# Power_Decoupling.net
KiCad netlist of a schematic drawn in Altium Designer
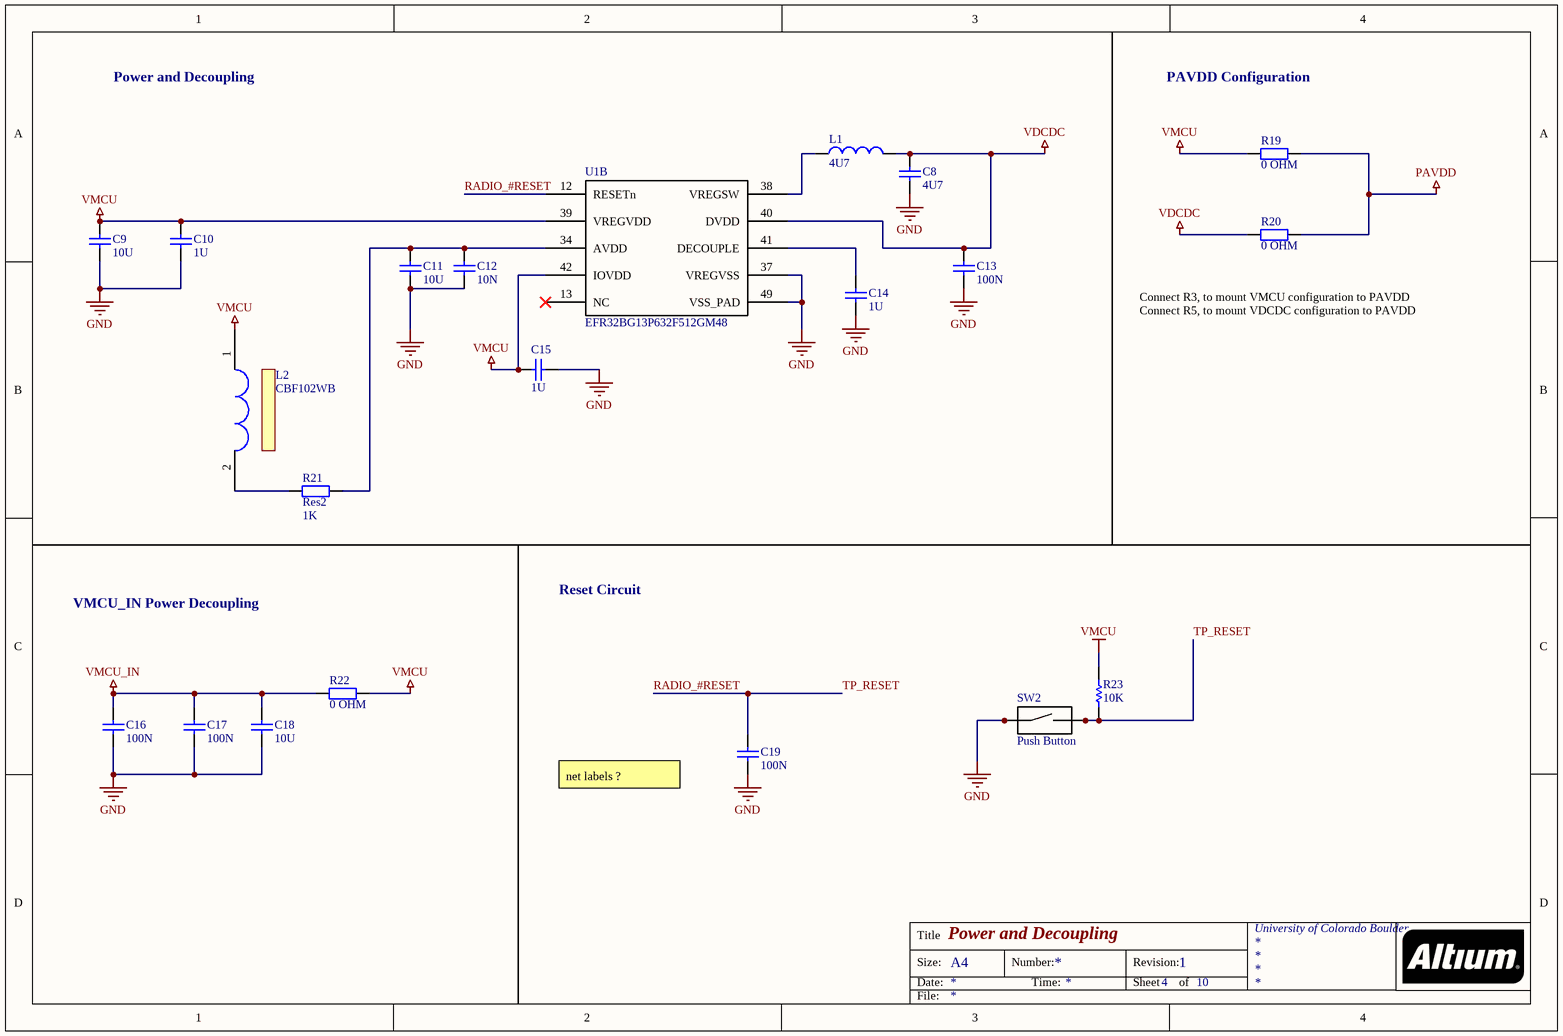
[diagram p0: Power_Decoupling.SchDoc]

(export (version "E")
  (design (tool "Eeschema 10.0.6"))
  (components
    (comp (ref "C8")
      (value "4U7")
      (footprint "1608[0603]")
      (description "CAP CER 4.7UF 25V X5R 0603")
      (fields
        (field (name "DIGI-KEY PART NUMBER") "1276-1900-1-ND")
        (field (name "MANUFACTURER") "Samsung Electro-Mechanics")
      )
      (libsource (lib "Miscellaneous Devices") (part "Cap"))
    )
    (comp (ref "C9")
      (value "10U")
      (footprint "1608[0603]")
      (description "CAP CER 10UF 6.3V X5R 0603")
      (fields
        (field (name "DIGI-KEY PART NUMBER") "1276-1119-1-ND")
        (field (name "MANUFACTURER") "Samsung Electro-Mechanics")
      )
      (libsource (lib "Miscellaneous Devices") (part "Cap"))
    )
    (comp (ref "C10")
      (value "1U")
      (footprint "RAD-0.3")
      (description "CAP CER 1UF 25V X5R 0603")
      (fields
        (field (name "DIGI-KEY PART NUMBER") "1276-1102-1-ND")
        (field (name "MANUFACTURER") "Samsung Electro-Mechanics")
      )
      (libsource (lib "Miscellaneous Devices") (part "Cap"))
    )
    (comp (ref "C11")
      (value "10U")
      (footprint "1608[0603]")
      (description "CAP CER 10UF 6.3V X5R 0603")
      (fields
        (field (name "DIGI-KEY PART NUMBER") "1276-1119-1-ND")
        (field (name "MANUFACTURER") "Samsung Electro-Mechanics")
      )
      (libsource (lib "Miscellaneous Devices") (part "Cap"))
    )
    (comp (ref "C12")
      (value "10N")
      (footprint "1608[0603]")
      (description "CAP CER 10000PF 16V X7R 0603")
      (fields (field (name "DIGI-KEY PART NUMBER") "399-7841-1-ND") (field (name "MANUFACTURER") "KEMET"))
      (libsource (lib "Miscellaneous Devices") (part "Cap"))
    )
    (comp (ref "C13")
      (value "100N")
      (footprint "1608[0603]")
      (description "CAP CER 0.1UF 16V X7R 0603")
      (fields
        (field (name "DIGI-KEY PART NUMBER") "1276-1005-1-ND")
        (field (name "MANUFACTURER") "Samsung Electro-Mechanics")
      )
      (libsource (lib "Miscellaneous Devices") (part "Cap"))
    )
    (comp (ref "C14")
      (value "1U")
      (footprint "1608[0603]")
      (description "CAP CER 1UF 25V X5R 0603")
      (fields
        (field (name "DIGI-KEY PART NUMBER") "1276-1102-1-ND")
        (field (name "MANUFACTURER") "Samsung Electro-Mechanics")
      )
      (libsource (lib "Miscellaneous Devices") (part "Cap"))
    )
    (comp (ref "C15")
      (value "1U")
      (footprint "1608[0603]")
      (description "CAP CER 1UF 25V X5R 0603")
      (fields
        (field (name "DIGI-KEY PART NUMBER") "1276-1102-1-ND")
        (field (name "MANUFACTURER") "Samsung Electro-Mechanics")
      )
      (libsource (lib "Miscellaneous Devices") (part "Cap"))
    )
    (comp (ref "C16")
      (value "100N")
      (footprint "1608[0603]")
      (description "CAP CER 0.1UF 16V X7R 0603")
      (fields
        (field (name "DIGI-KEY PART NUMBER") "1276-1005-1-ND")
        (field (name "MANUFACTURER") "Samsung Electro-Mechanics")
      )
      (libsource (lib "Miscellaneous Devices") (part "Cap"))
    )
    (comp (ref "C17")
      (value "100N")
      (footprint "1608[0603]")
      (description "CAP CER 0.1UF 16V X7R 0603")
      (fields
        (field (name "DIGI-KEY PART NUMBER") "1276-1005-1-ND")
        (field (name "MANUFACTURER") "Samsung Electro-Mechanics")
      )
      (libsource (lib "Miscellaneous Devices") (part "Cap"))
    )
    (comp (ref "C18")
      (value "10U")
      (footprint "1608[0603]")
      (description "CAP CER 10UF 6.3V X5R 0603")
      (fields
        (field (name "DIGI-KEY PART NUMBER") "490-12538-1-ND")
        (field (name "MANUFACTURER") "Murata Electronics")
      )
      (libsource (lib "Miscellaneous Devices") (part "Cap"))
    )
    (comp (ref "C19")
      (value "100N")
      (footprint "1608[0603]")
      (description "CAP CER 0.1UF 16V X7R 0603")
      (fields
        (field (name "DIGI-KEY PART NUMBER") "1276-1005-1-ND")
        (field (name "MANUFACTURER") "Samsung Electro-Mechanics")
      )
      (libsource (lib "Miscellaneous Devices") (part "Cap"))
    )
    (comp (ref "L1")
      (value "4U7")
      (footprint "0402-A")
      (description "FIXED IND 4.7UH 1.25A 130 MOHM")
      (fields
        (field (name "MOUSER PART NUMBER") "81-LQH3NPN4R7MM0L")
        (field (name "MANUFACTURER") "Murata Electronics")
      )
      (libsource (lib "Miscellaneous Devices") (part "Inductor"))
    )
    (comp (ref "L2")
      (value "CBF102WB")
      (footprint "*CAPC0603X56N")
      (description "FERRITE BEAD 1 KOHM 0603 1LN")
      (fields
        (field (name "DIGI-KEY PART NUMBER") "732-4484-1-ND")
        (field (name "MANUFACTURER") "Wurth Electronics Inc.")
      )
      (libsource (lib "LPEDT_Project_Library") (part "COMPONENT_1"))
    )
    (comp (ref "R19")
      (value "0 OHM")
      (footprint "AXIAL-0.4")
      (description "RES SMD 0 OHM JUMPER 1/10W 0603")
      (fields (field (name "DIGI-KEY PART NUMBER") "311-0.0GRCT-ND") (field (name "MANUFACTURER") "Yageo"))
      (libsource (lib "Miscellaneous Devices") (part "Res2"))
    )
    (comp (ref "R20")
      (value "0 OHM")
      (footprint "AXIAL-0.4")
      (description "RES SMD 0 OHM JUMPER 1/10W 0603")
      (fields (field (name "DIGI-KEY PART NUMBER") "311-0.0GRCT-ND") (field (name "MANUFACTURER") "Yageo"))
      (libsource (lib "Miscellaneous Devices") (part "Res2"))
    )
    (comp (ref "R21")
      (value "Res2")
      (footprint "AXIAL-0.4")
      (description "Resistor")
      (fields (field (name "ALTIUM_VALUE") "1K") (field (name "PUBLISHER") "Altium Limited"))
      (libsource (lib "Miscellaneous Devices") (part "Res2"))
    )
    (comp (ref "R22")
      (value "0 OHM")
      (footprint "1608[0603]")
      (description "RES SMD 0 OHM JUMPER 1/10W 0603")
      (fields (field (name "DIGI-KEY PART NUMBER") "311-0.0GRCT-ND") (field (name "MANUFACTURER") "Yageo"))
      (libsource (lib "Miscellaneous Devices") (part "Res2"))
    )
    (comp (ref "R23")
      (value "10K")
      (footprint "1608[0603]")
      (description "RES 10K OHM 1% 1/8W 0603")
      (fields
        (field (name "DIGI-KEY PART NUMBER") "RNCP0603FTD10K0CT-ND")
        (field (name "MANUFACTURER") "Stackpole Electronics Inc")
      )
      (libsource (lib "Miscellaneous Devices") (part "Res1"))
    )
    (comp (ref "SW2")
      (value "Push Button")
      (footprint "Push Button")
      (description "SWITCH TACTILE SPST-NO 0.05A 24V")
      (fields
        (field (name "DIGI-KEY PART NUMBER") "450-2058-1-ND")
        (field (name "MANUFACTURER") "TE Connectivity ALCOSWITCH Switches")
      )
      (libsource (lib "Hydrated_Buffs") (part "Push Button"))
    )
    (comp (ref "U1")
      (value "EFR32BG13P632F512GM48")
      (footprint "*QFN50P700X700X90-49N")
      (description "MCU")
      (fields
        (field (name "MANUFACTURER") "Silicon Labs")
        (field (name "MANUFACTURER PART NUMBER") "EFR32BG13P632F512GM48-BR")
      )
      (libsource (lib "EFR32BG13") (part "EFR32BG13"))
    )
  )
  (nets
    (net (code "1") (name "/RADIO_#RESET") (class "Default")
      (node (ref "C19") (pin "2") (pinfunction "2_2") (pintype "passive"))
      (node (ref "R23") (pin "1") (pinfunction "1_1") (pintype "passive"))
      (node (ref "SW2") (pin "1") (pinfunction "2_1") (pintype "passive"))
      (node (ref "SW2") (pin "2") (pinfunction "2_2") (pintype "passive"))
      (node (ref "U1") (pin "12") (pinfunction "RESETn_12") (pintype "passive"))
    )
    (net (code "2") (name "GND") (class "Default")
      (node (ref "C10") (pin "1") (pinfunction "1_1") (pintype "passive"))
      (node (ref "C11") (pin "1") (pinfunction "1_1") (pintype "passive"))
      (node (ref "C12") (pin "1") (pinfunction "1_1") (pintype "passive"))
      (node (ref "C13") (pin "1") (pinfunction "1_1") (pintype "passive"))
      (node (ref "C14") (pin "1") (pinfunction "1_1") (pintype "passive"))
      (node (ref "C15") (pin "1") (pinfunction "1_1") (pintype "passive"))
      (node (ref "C16") (pin "1") (pinfunction "1_1") (pintype "passive"))
      (node (ref "C17") (pin "1") (pinfunction "1_1") (pintype "passive"))
      (node (ref "C18") (pin "1") (pinfunction "1_1") (pintype "passive"))
      (node (ref "C19") (pin "1") (pinfunction "1_1") (pintype "passive"))
      (node (ref "C8") (pin "1") (pinfunction "1_1") (pintype "passive"))
      (node (ref "C9") (pin "1") (pinfunction "1_1") (pintype "passive"))
      (node (ref "SW2") (pin "3") (pinfunction "1_3") (pintype "passive"))
      (node (ref "SW2") (pin "4") (pinfunction "1_4") (pintype "passive"))
      (node (ref "U1") (pin "37") (pinfunction "VREGVSS_37") (pintype "passive"))
      (node (ref "U1") (pin "49") (pinfunction "VSS_PAD_49") (pintype "passive"))
    )
    (net (code "3") (name "Net-(L2-Pad2)") (class "Default")
      (node (ref "L2") (pin "2") (pintype "passive"))
      (node (ref "R21") (pin "1") (pinfunction "1_1") (pintype "passive"))
    )
    (net (code "4") (name "Net-(U1B-AVDD)") (class "Default")
      (node (ref "C11") (pin "2") (pinfunction "2_2") (pintype "passive"))
      (node (ref "C12") (pin "2") (pinfunction "2_2") (pintype "passive"))
      (node (ref "R21") (pin "2") (pinfunction "2_2") (pintype "passive"))
      (node (ref "U1") (pin "34") (pinfunction "AVDD_34") (pintype "passive"))
    )
    (net (code "5") (name "Net-(U1B-DECOUPLE)") (class "Default")
      (node (ref "C14") (pin "2") (pinfunction "2_2") (pintype "passive"))
      (node (ref "U1") (pin "41") (pinfunction "DECOUPLE_41") (pintype "passive"))
    )
    (net (code "6") (name "Net-(U1B-VREGSW)") (class "Default")
      (node (ref "L1") (pin "1") (pinfunction "1_1") (pintype "passive"))
      (node (ref "U1") (pin "38") (pinfunction "VREGSW_38") (pintype "passive"))
    )
    (net (code "7") (name "PAVDD") (class "Default")
      (node (ref "R19") (pin "2") (pinfunction "2_2") (pintype "passive"))
      (node (ref "R20") (pin "2") (pinfunction "2_2") (pintype "passive"))
    )
    (net (code "8") (name "VDCDC") (class "Default")
      (node (ref "C13") (pin "2") (pinfunction "2_2") (pintype "passive"))
      (node (ref "C8") (pin "2") (pinfunction "2_2") (pintype "passive"))
      (node (ref "L1") (pin "2") (pinfunction "2_2") (pintype "passive"))
      (node (ref "R20") (pin "1") (pinfunction "1_1") (pintype "passive"))
      (node (ref "U1") (pin "40") (pinfunction "DVDD_40") (pintype "passive"))
    )
    (net (code "9") (name "VMCU") (class "Default")
      (node (ref "C10") (pin "2") (pinfunction "2_2") (pintype "passive"))
      (node (ref "C15") (pin "2") (pinfunction "2_2") (pintype "passive"))
      (node (ref "C9") (pin "2") (pinfunction "2_2") (pintype "passive"))
      (node (ref "L2") (pin "1") (pintype "passive"))
      (node (ref "R19") (pin "1") (pinfunction "1_1") (pintype "passive"))
      (node (ref "R22") (pin "2") (pinfunction "2_2") (pintype "passive"))
      (node (ref "R23") (pin "2") (pinfunction "2_2") (pintype "passive"))
      (node (ref "U1") (pin "39") (pinfunction "VREGVDD_39") (pintype "passive"))
      (node (ref "U1") (pin "42") (pinfunction "IOVDD_42") (pintype "passive"))
    )
    (net (code "10") (name "VMCU_IN") (class "Default")
      (node (ref "C16") (pin "2") (pinfunction "2_2") (pintype "passive"))
      (node (ref "C17") (pin "2") (pinfunction "2_2") (pintype "passive"))
      (node (ref "C18") (pin "2") (pinfunction "2_2") (pintype "passive"))
      (node (ref "R22") (pin "1") (pinfunction "1_1") (pintype "passive"))
    )
    (net (code "11") (name "unconnected-(U1B-NC-Pad13)") (class "Default")
      (node (ref "U1") (pin "13") (pinfunction "NC_13") (pintype "passive+no_connect"))
    )
  )
)
